# Qwiic_Multi_Port_Board.net
KiCad netlist of a schematic drawn in EAGLE
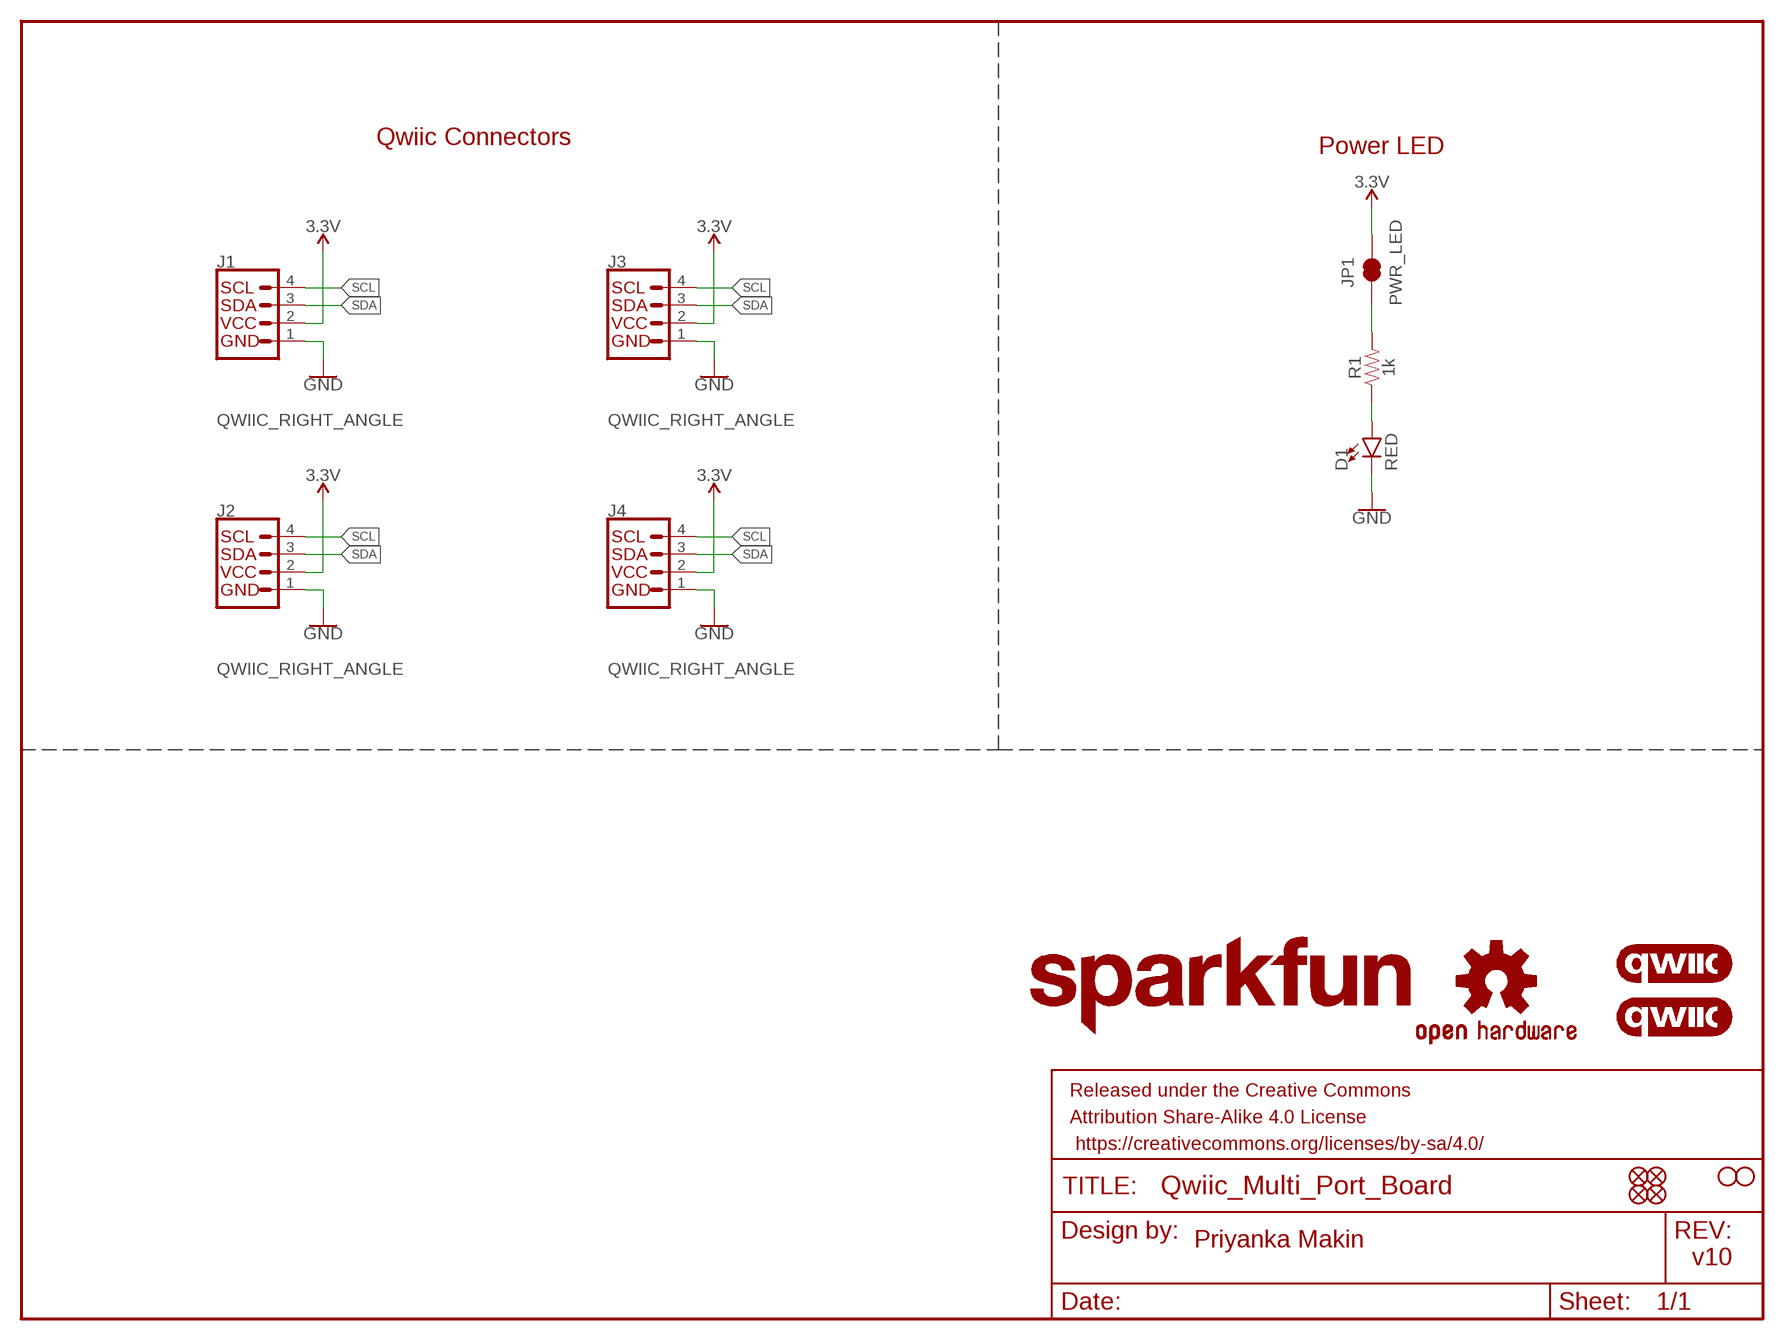
[diagram p0: schematic, sheet 1]

(export (version "E")
  (design (tool "Eeschema 10.0.6"))
  (components
    (comp (ref "D1")
      (value "RED")
      (footprint "eagle-import:LED-0603")
      (libsource (lib "eagle-import") (part "LED-RED0603"))
    )
    (comp (ref "FD1")
      (value "FIDUCIAL1X2")
      (footprint "eagle-import:FIDUCIAL-1X2")
      (libsource (lib "eagle-import") (part "FIDUCIAL1X2"))
    )
    (comp (ref "FD2")
      (value "FIDUCIAL1X2")
      (footprint "eagle-import:FIDUCIAL-1X2")
      (libsource (lib "eagle-import") (part "FIDUCIAL1X2"))
    )
    (comp (ref "FD3")
      (value "FIDUCIAL1X2")
      (footprint "eagle-import:FIDUCIAL-1X2")
      (libsource (lib "eagle-import") (part "FIDUCIAL1X2"))
    )
    (comp (ref "FD4")
      (value "FIDUCIAL1X2")
      (footprint "eagle-import:FIDUCIAL-1X2")
      (libsource (lib "eagle-import") (part "FIDUCIAL1X2"))
    )
    (comp (ref "FRAME1")
      (value "FRAME-LETTER")
      (footprint "eagle-import:CREATIVE_COMMONS")
      (libsource (lib "eagle-import") (part "FRAME-LETTER"))
    )
    (comp (ref "H1")
      (value "STAND-OFFTIGHT")
      (footprint "eagle-import:STAND-OFF-TIGHT")
      (libsource (lib "eagle-import") (part "STAND-OFFTIGHT"))
    )
    (comp (ref "H2")
      (value "STAND-OFFTIGHT")
      (footprint "eagle-import:STAND-OFF-TIGHT")
      (libsource (lib "eagle-import") (part "STAND-OFFTIGHT"))
    )
    (comp (ref "J1")
      (value "QWIIC_RIGHT_ANGLE")
      (footprint "eagle-import:JST04_1MM_RA")
      (libsource (lib "eagle-import") (part "QWIIC_CONNECTORJS-1MM"))
    )
    (comp (ref "J2")
      (value "QWIIC_RIGHT_ANGLE")
      (footprint "eagle-import:JST04_1MM_RA")
      (libsource (lib "eagle-import") (part "QWIIC_CONNECTORJS-1MM"))
    )
    (comp (ref "J3")
      (value "QWIIC_RIGHT_ANGLE")
      (footprint "eagle-import:JST04_1MM_RA")
      (libsource (lib "eagle-import") (part "QWIIC_CONNECTORJS-1MM"))
    )
    (comp (ref "J4")
      (value "QWIIC_RIGHT_ANGLE")
      (footprint "eagle-import:JST04_1MM_RA")
      (libsource (lib "eagle-import") (part "QWIIC_CONNECTORJS-1MM"))
    )
    (comp (ref "JP1")
      (value "PWR_LED")
      (footprint "eagle-import:SMT-JUMPER_2_NC_TRACE_SILK")
      (libsource (lib "eagle-import") (part "JUMPER-SMT_2_NC_TRACE_SILK"))
    )
    (comp (ref "LOGO1")
      (value "QWIIC_LOGO_5MM")
      (footprint "eagle-import:QWIIC_5MM")
      (libsource (lib "eagle-import") (part "QWIIC_LOGO_5MM"))
    )
    (comp (ref "LOGO2")
      (value "QWIIC_LOGO_5MM")
      (footprint "eagle-import:QWIIC_5MM")
      (libsource (lib "eagle-import") (part "QWIIC_LOGO_5MM"))
    )
    (comp (ref "LOGO3")
      (value "OSHW-LOGOS")
      (footprint "eagle-import:OSHW-LOGO-S")
      (libsource (lib "eagle-import") (part "OSHW-LOGOS"))
    )
    (comp (ref "LOGO4")
      (value "SFE_LOGO_NAME.2_INCH")
      (footprint "eagle-import:SFE_LOGO_NAME_.2")
      (libsource (lib "eagle-import") (part "SFE_LOGO_NAME.2_INCH"))
    )
    (comp (ref "R1")
      (value "1k")
      (footprint "eagle-import:0603")
      (libsource (lib "eagle-import") (part "1KOHM-0603-1/10W-1%"))
    )
  )
  (nets
    (net (code "1") (name "3.3V") (class "Default")
      (node (ref "J1") (pin "2") (pinfunction "2_2") (pintype "power_in"))
      (node (ref "J2") (pin "2") (pinfunction "2_2") (pintype "power_in"))
      (node (ref "J3") (pin "2") (pinfunction "2_2") (pintype "power_in"))
      (node (ref "J4") (pin "2") (pinfunction "2_2") (pintype "power_in"))
      (node (ref "JP1") (pin "2") (pinfunction "2_2") (pintype "passive"))
    )
    (net (code "2") (name "GND") (class "Default")
      (node (ref "D1") (pin "C") (pinfunction "C_C") (pintype "passive"))
      (node (ref "J1") (pin "1") (pinfunction "1_1") (pintype "power_in"))
      (node (ref "J2") (pin "1") (pinfunction "1_1") (pintype "power_in"))
      (node (ref "J3") (pin "1") (pinfunction "1_1") (pintype "power_in"))
      (node (ref "J4") (pin "1") (pinfunction "1_1") (pintype "power_in"))
    )
    (net (code "3") (name "Net-(D1-PadA)") (class "Default")
      (node (ref "D1") (pin "A") (pinfunction "A_A") (pintype "passive"))
      (node (ref "R1") (pin "1") (pinfunction "1_1") (pintype "passive"))
    )
    (net (code "4") (name "Net-(JP1-Pad1)") (class "Default")
      (node (ref "JP1") (pin "1") (pinfunction "1_1") (pintype "passive"))
      (node (ref "R1") (pin "2") (pinfunction "2_2") (pintype "passive"))
    )
    (net (code "5") (name "SCL") (class "Default")
      (node (ref "J1") (pin "4") (pinfunction "4_4") (pintype "passive"))
      (node (ref "J2") (pin "4") (pinfunction "4_4") (pintype "passive"))
      (node (ref "J3") (pin "4") (pinfunction "4_4") (pintype "passive"))
      (node (ref "J4") (pin "4") (pinfunction "4_4") (pintype "passive"))
    )
    (net (code "6") (name "SDA") (class "Default")
      (node (ref "J1") (pin "3") (pinfunction "3_3") (pintype "passive"))
      (node (ref "J2") (pin "3") (pinfunction "3_3") (pintype "passive"))
      (node (ref "J3") (pin "3") (pinfunction "3_3") (pintype "passive"))
      (node (ref "J4") (pin "3") (pinfunction "3_3") (pintype "passive"))
    )
  )
)
